# LV_Schematic.net
KiCad netlist of a schematic drawn in Altium Designer
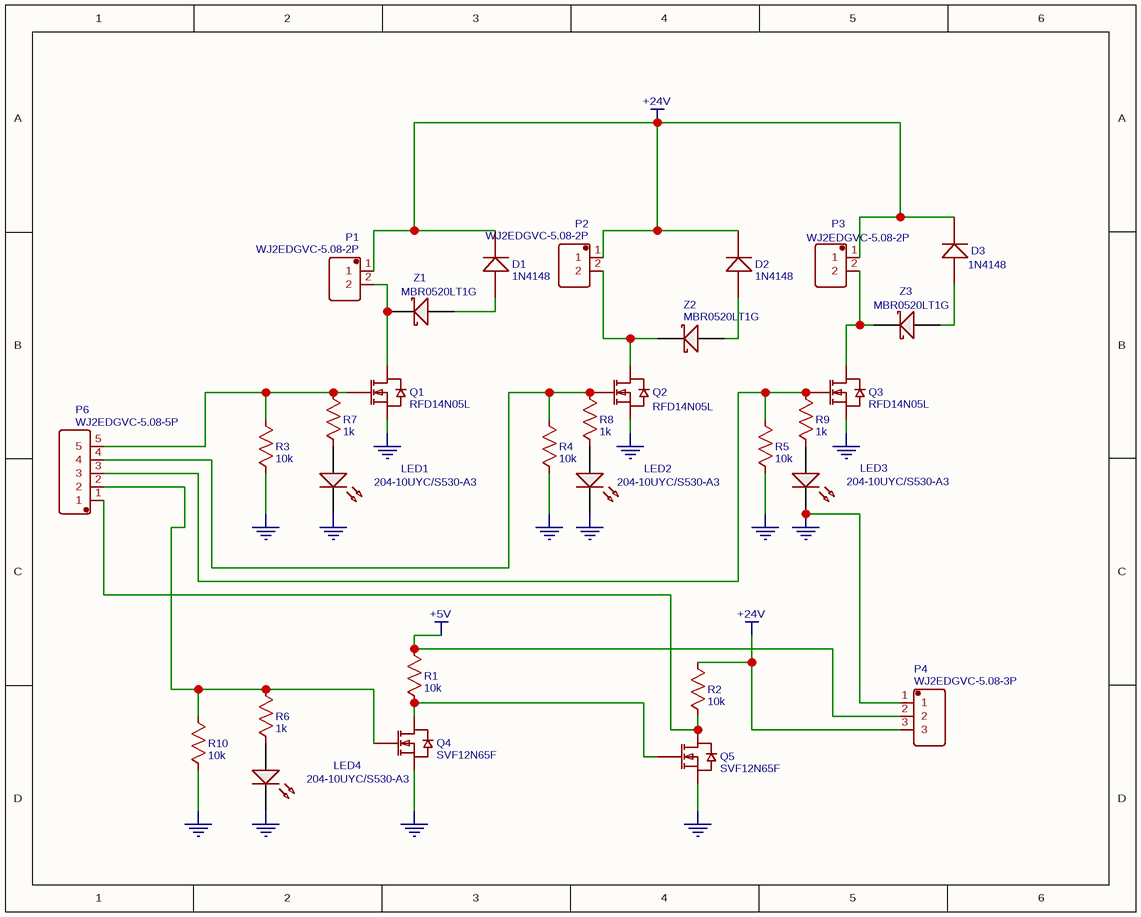
[diagram p0: LV+Schematic.schdoc]

(export (version "E")
  (design (tool "Eeschema 10.0.6"))
  (components
    (comp (ref "D1") (value "1N4148") (libsource (lib "") (part "root_1___1")))
    (comp (ref "D2") (value "1N4148") (libsource (lib "") (part "root_1___1")))
    (comp (ref "D3") (value "1N4148") (libsource (lib "") (part "root_1___1")))
    (comp (ref "LED1") (value "204-10UYC/S530-A3") (libsource (lib "altium-import") (part "root_3__")))
    (comp (ref "LED2") (value "204-10UYC/S530-A3") (libsource (lib "altium-import") (part "root_3__")))
    (comp (ref "LED3") (value "204-10UYC/S530-A3") (libsource (lib "altium-import") (part "root_3__")))
    (comp (ref "LED4") (value "204-10UYC/S530-A3") (libsource (lib "altium-import") (part "root_3__")))
    (comp (ref "P1")
      (value "WJ2EDGVC-5.08-2P")
      (fields (field (name "BOM_MANUFACTURER PART") "?"))
      (libsource (lib "") (part "root_0___1"))
    )
    (comp (ref "P2")
      (value "WJ2EDGVC-5.08-2P")
      (fields (field (name "BOM_MANUFACTURER PART") "?"))
      (libsource (lib "") (part "root_0___1"))
    )
    (comp (ref "P3")
      (value "WJ2EDGVC-5.08-2P")
      (fields (field (name "BOM_MANUFACTURER PART") "?"))
      (libsource (lib "") (part "root_0___1"))
    )
    (comp (ref "P4")
      (value "WJ2EDGVC-5.08-3P")
      (fields (field (name "BOM_MANUFACTURER PART") "?"))
      (libsource (lib "") (part "root_0___3"))
    )
    (comp (ref "P6")
      (value "WJ2EDGVC-5.08-5P")
      (fields (field (name "BOM_MANUFACTURER PART") "?"))
      (libsource (lib "altium-import") (part "root_2__"))
    )
    (comp (ref "Q1")
      (value "RFD14N05L")
      (fields (field (name "BOM_MANUFACTURER PART") "SVF12N65F"))
      (libsource (lib "altium-import") (part "root_0__"))
    )
    (comp (ref "Q2")
      (value "RFD14N05L")
      (fields (field (name "BOM_MANUFACTURER PART") "SVF12N65F"))
      (libsource (lib "altium-import") (part "root_0__"))
    )
    (comp (ref "Q3")
      (value "RFD14N05L")
      (fields (field (name "BOM_MANUFACTURER PART") "SVF12N65F"))
      (libsource (lib "altium-import") (part "root_0__"))
    )
    (comp (ref "Q4") (value "SVF12N65F") (libsource (lib "altium-import") (part "root_0__")))
    (comp (ref "Q5") (value "SVF12N65F") (libsource (lib "altium-import") (part "root_0__")))
    (comp (ref "R1")
      (value "10k")
      (fields (field (name "BOM_MANUFACTURER PART") "?"))
      (libsource (lib "altium-import") (part "root_1__"))
    )
    (comp (ref "R2")
      (value "10k")
      (fields (field (name "BOM_MANUFACTURER PART") "?"))
      (libsource (lib "altium-import") (part "root_1__"))
    )
    (comp (ref "R3")
      (value "10k")
      (fields (field (name "BOM_MANUFACTURER PART") "?"))
      (libsource (lib "altium-import") (part "root_1__"))
    )
    (comp (ref "R4")
      (value "10k")
      (fields (field (name "BOM_MANUFACTURER PART") "?"))
      (libsource (lib "altium-import") (part "root_1__"))
    )
    (comp (ref "R5")
      (value "10k")
      (fields (field (name "BOM_MANUFACTURER PART") "?"))
      (libsource (lib "altium-import") (part "root_1__"))
    )
    (comp (ref "R6")
      (value "1k")
      (fields (field (name "BOM_MANUFACTURER PART") "?"))
      (libsource (lib "altium-import") (part "root_1__"))
    )
    (comp (ref "R7")
      (value "1k")
      (fields (field (name "BOM_MANUFACTURER PART") "?"))
      (libsource (lib "altium-import") (part "root_1__"))
    )
    (comp (ref "R8")
      (value "1k")
      (fields (field (name "BOM_MANUFACTURER PART") "?"))
      (libsource (lib "altium-import") (part "root_1__"))
    )
    (comp (ref "R9")
      (value "1k")
      (fields (field (name "BOM_MANUFACTURER PART") "?"))
      (libsource (lib "altium-import") (part "root_1__"))
    )
    (comp (ref "R10")
      (value "10k")
      (fields (field (name "BOM_MANUFACTURER PART") "?"))
      (libsource (lib "altium-import") (part "root_1__"))
    )
    (comp (ref "Z1") (value "MBR0520LT1G") (libsource (lib "") (part "root_0___2")))
    (comp (ref "Z2") (value "MBR0520LT1G") (libsource (lib "") (part "root_0___2")))
    (comp (ref "Z3") (value "MBR0520LT1G") (libsource (lib "") (part "root_0___2")))
  )
  (nets
    (net (code "1") (name "+5V") (class "Default")
      (node (ref "P4") (pin "2") (pinfunction "2_2") (pintype "passive"))
      (node (ref "R1") (pin "2") (pinfunction "2_2") (pintype "passive"))
    )
    (net (code "2") (name "+24V") (class "Default")
      (node (ref "D1") (pin "2") (pinfunction "K_2") (pintype "passive"))
      (node (ref "D2") (pin "2") (pinfunction "K_2") (pintype "passive"))
      (node (ref "D3") (pin "2") (pinfunction "K_2") (pintype "passive"))
      (node (ref "P1") (pin "1") (pinfunction "1_1") (pintype "passive"))
      (node (ref "P2") (pin "1") (pinfunction "1_1") (pintype "passive"))
      (node (ref "P3") (pin "1") (pinfunction "1_1") (pintype "passive"))
      (node (ref "P4") (pin "3") (pinfunction "3_3") (pintype "passive"))
      (node (ref "R2") (pin "2") (pinfunction "2_2") (pintype "passive"))
    )
    (net (code "3") (name "GND") (class "Default")
      (node (ref "LED1") (pin "2") (pinfunction "C_2") (pintype "passive"))
      (node (ref "LED2") (pin "2") (pinfunction "C_2") (pintype "passive"))
      (node (ref "LED3") (pin "2") (pinfunction "C_2") (pintype "passive"))
      (node (ref "LED4") (pin "2") (pinfunction "C_2") (pintype "passive"))
      (node (ref "P4") (pin "1") (pinfunction "1_1") (pintype "passive"))
      (node (ref "Q1") (pin "3") (pinfunction "S_3") (pintype "passive"))
      (node (ref "Q2") (pin "3") (pinfunction "S_3") (pintype "passive"))
      (node (ref "Q3") (pin "3") (pinfunction "S_3") (pintype "passive"))
      (node (ref "Q4") (pin "3") (pinfunction "S_3") (pintype "passive"))
      (node (ref "Q5") (pin "3") (pinfunction "S_3") (pintype "passive"))
      (node (ref "R10") (pin "1") (pinfunction "1_1") (pintype "passive"))
      (node (ref "R3") (pin "1") (pinfunction "1_1") (pintype "passive"))
      (node (ref "R4") (pin "1") (pinfunction "1_1") (pintype "passive"))
      (node (ref "R5") (pin "1") (pinfunction "1_1") (pintype "passive"))
    )
    (net (code "4") (name "Net-(D1-A)") (class "Default")
      (node (ref "D1") (pin "1") (pinfunction "A_1") (pintype "passive"))
      (node (ref "Z1") (pin "1") (pinfunction "A_1") (pintype "passive"))
    )
    (net (code "5") (name "Net-(D2-A)") (class "Default")
      (node (ref "D2") (pin "1") (pinfunction "A_1") (pintype "passive"))
      (node (ref "Z2") (pin "1") (pinfunction "A_1") (pintype "passive"))
    )
    (net (code "6") (name "Net-(D3-A)") (class "Default")
      (node (ref "D3") (pin "1") (pinfunction "A_1") (pintype "passive"))
      (node (ref "Z3") (pin "1") (pinfunction "A_1") (pintype "passive"))
    )
    (net (code "7") (name "Net-(LED1-A)") (class "Default")
      (node (ref "LED1") (pin "1") (pinfunction "A_1") (pintype "passive"))
      (node (ref "R7") (pin "1") (pinfunction "1_1") (pintype "passive"))
    )
    (net (code "8") (name "Net-(LED2-A)") (class "Default")
      (node (ref "LED2") (pin "1") (pinfunction "A_1") (pintype "passive"))
      (node (ref "R8") (pin "1") (pinfunction "1_1") (pintype "passive"))
    )
    (net (code "9") (name "Net-(LED3-A)") (class "Default")
      (node (ref "LED3") (pin "1") (pinfunction "A_1") (pintype "passive"))
      (node (ref "R9") (pin "1") (pinfunction "1_1") (pintype "passive"))
    )
    (net (code "10") (name "Net-(LED4-A)") (class "Default")
      (node (ref "LED4") (pin "1") (pinfunction "A_1") (pintype "passive"))
      (node (ref "R6") (pin "1") (pinfunction "1_1") (pintype "passive"))
    )
    (net (code "11") (name "Net-(Q1-D)") (class "Default")
      (node (ref "P1") (pin "2") (pinfunction "2_2") (pintype "passive"))
      (node (ref "Q1") (pin "2") (pinfunction "D_2") (pintype "passive"))
      (node (ref "Z1") (pin "2") (pinfunction "K_2") (pintype "passive"))
    )
    (net (code "12") (name "Net-(Q1-G)") (class "Default")
      (node (ref "P6") (pin "5") (pinfunction "5_5") (pintype "passive"))
      (node (ref "Q1") (pin "1") (pinfunction "G_1") (pintype "passive"))
      (node (ref "R3") (pin "2") (pinfunction "2_2") (pintype "passive"))
      (node (ref "R7") (pin "2") (pinfunction "2_2") (pintype "passive"))
    )
    (net (code "13") (name "Net-(Q2-D)") (class "Default")
      (node (ref "P2") (pin "2") (pinfunction "2_2") (pintype "passive"))
      (node (ref "Q2") (pin "2") (pinfunction "D_2") (pintype "passive"))
      (node (ref "Z2") (pin "2") (pinfunction "K_2") (pintype "passive"))
    )
    (net (code "14") (name "Net-(Q2-G)") (class "Default")
      (node (ref "P6") (pin "4") (pinfunction "4_4") (pintype "passive"))
      (node (ref "Q2") (pin "1") (pinfunction "G_1") (pintype "passive"))
      (node (ref "R4") (pin "2") (pinfunction "2_2") (pintype "passive"))
      (node (ref "R8") (pin "2") (pinfunction "2_2") (pintype "passive"))
    )
    (net (code "15") (name "Net-(Q3-D)") (class "Default")
      (node (ref "P3") (pin "2") (pinfunction "2_2") (pintype "passive"))
      (node (ref "Q3") (pin "2") (pinfunction "D_2") (pintype "passive"))
      (node (ref "Z3") (pin "2") (pinfunction "K_2") (pintype "passive"))
    )
    (net (code "16") (name "Net-(Q3-G)") (class "Default")
      (node (ref "P6") (pin "3") (pinfunction "3_3") (pintype "passive"))
      (node (ref "Q3") (pin "1") (pinfunction "G_1") (pintype "passive"))
      (node (ref "R5") (pin "2") (pinfunction "2_2") (pintype "passive"))
      (node (ref "R9") (pin "2") (pinfunction "2_2") (pintype "passive"))
    )
    (net (code "17") (name "Net-(Q4-D)") (class "Default")
      (node (ref "Q4") (pin "2") (pinfunction "D_2") (pintype "passive"))
      (node (ref "Q5") (pin "1") (pinfunction "G_1") (pintype "passive"))
      (node (ref "R1") (pin "1") (pinfunction "1_1") (pintype "passive"))
    )
    (net (code "18") (name "Net-(Q4-G)") (class "Default")
      (node (ref "P6") (pin "2") (pinfunction "2_2") (pintype "passive"))
      (node (ref "Q4") (pin "1") (pinfunction "G_1") (pintype "passive"))
      (node (ref "R10") (pin "2") (pinfunction "2_2") (pintype "passive"))
      (node (ref "R6") (pin "2") (pinfunction "2_2") (pintype "passive"))
    )
    (net (code "19") (name "Net-(Q5-D)") (class "Default")
      (node (ref "P6") (pin "1") (pinfunction "1_1") (pintype "passive"))
      (node (ref "Q5") (pin "2") (pinfunction "D_2") (pintype "passive"))
      (node (ref "R2") (pin "1") (pinfunction "1_1") (pintype "passive"))
    )
  )
)
